# UserClock.net
KiCad netlist of a schematic drawn in Altium Designer
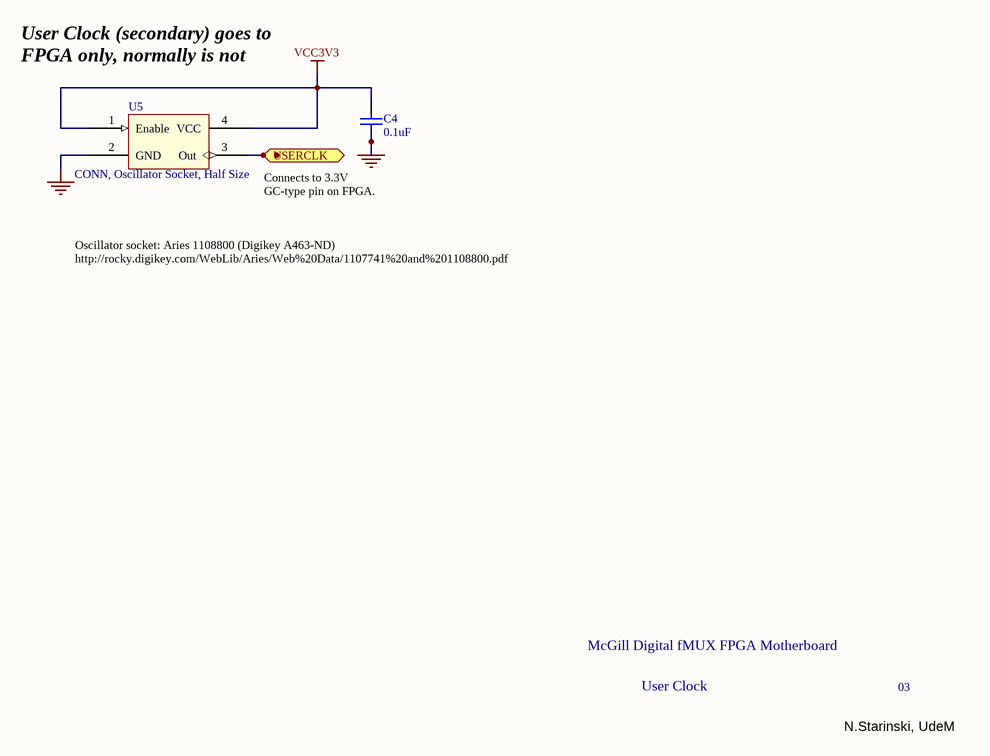
[diagram p0: UserClock.SchDoc]

(export (version "E")
  (design (tool "Eeschema 10.0.6"))
  (components
    (comp (ref "C4")
      (value "0.1uF")
      (footprint "CC1608-0603")
      (description "Capacitor (Semiconductor SIM Model)")
      (fields (field (name "PUBLISHER") "Altium Limited"))
      (libsource (lib "Miscellaneous Devices") (part "Cap Semi"))
    )
    (comp (ref "U5")
      (value "CONN, Oscillator Socket, Half Size")
      (footprint "DIP_Osc")
      (description "1108800 ARIES Oscillator Socket")
      (libsource (lib "MyComp1") (part "Osc_Socket"))
    )
  )
  (nets
    (net (code "1") (name "/USERCLK") (class "Default")
      (node (ref "U5") (pin "3") (pinfunction "Out_3") (pintype "output"))
    )
    (net (code "2") (name "GND") (class "Default")
      (node (ref "C4") (pin "1") (pinfunction "1_1") (pintype "passive"))
      (node (ref "U5") (pin "2") (pinfunction "GND_2") (pintype "power_in"))
    )
    (net (code "3") (name "VCC3V3") (class "Default")
      (node (ref "C4") (pin "2") (pinfunction "2_2") (pintype "passive"))
      (node (ref "U5") (pin "1") (pinfunction "Enable_1") (pintype "input"))
      (node (ref "U5") (pin "4") (pinfunction "VCC_4") (pintype "power_in"))
    )
  )
)
